# acq07.net
KiCad netlist of a schematic drawn in EAGLE
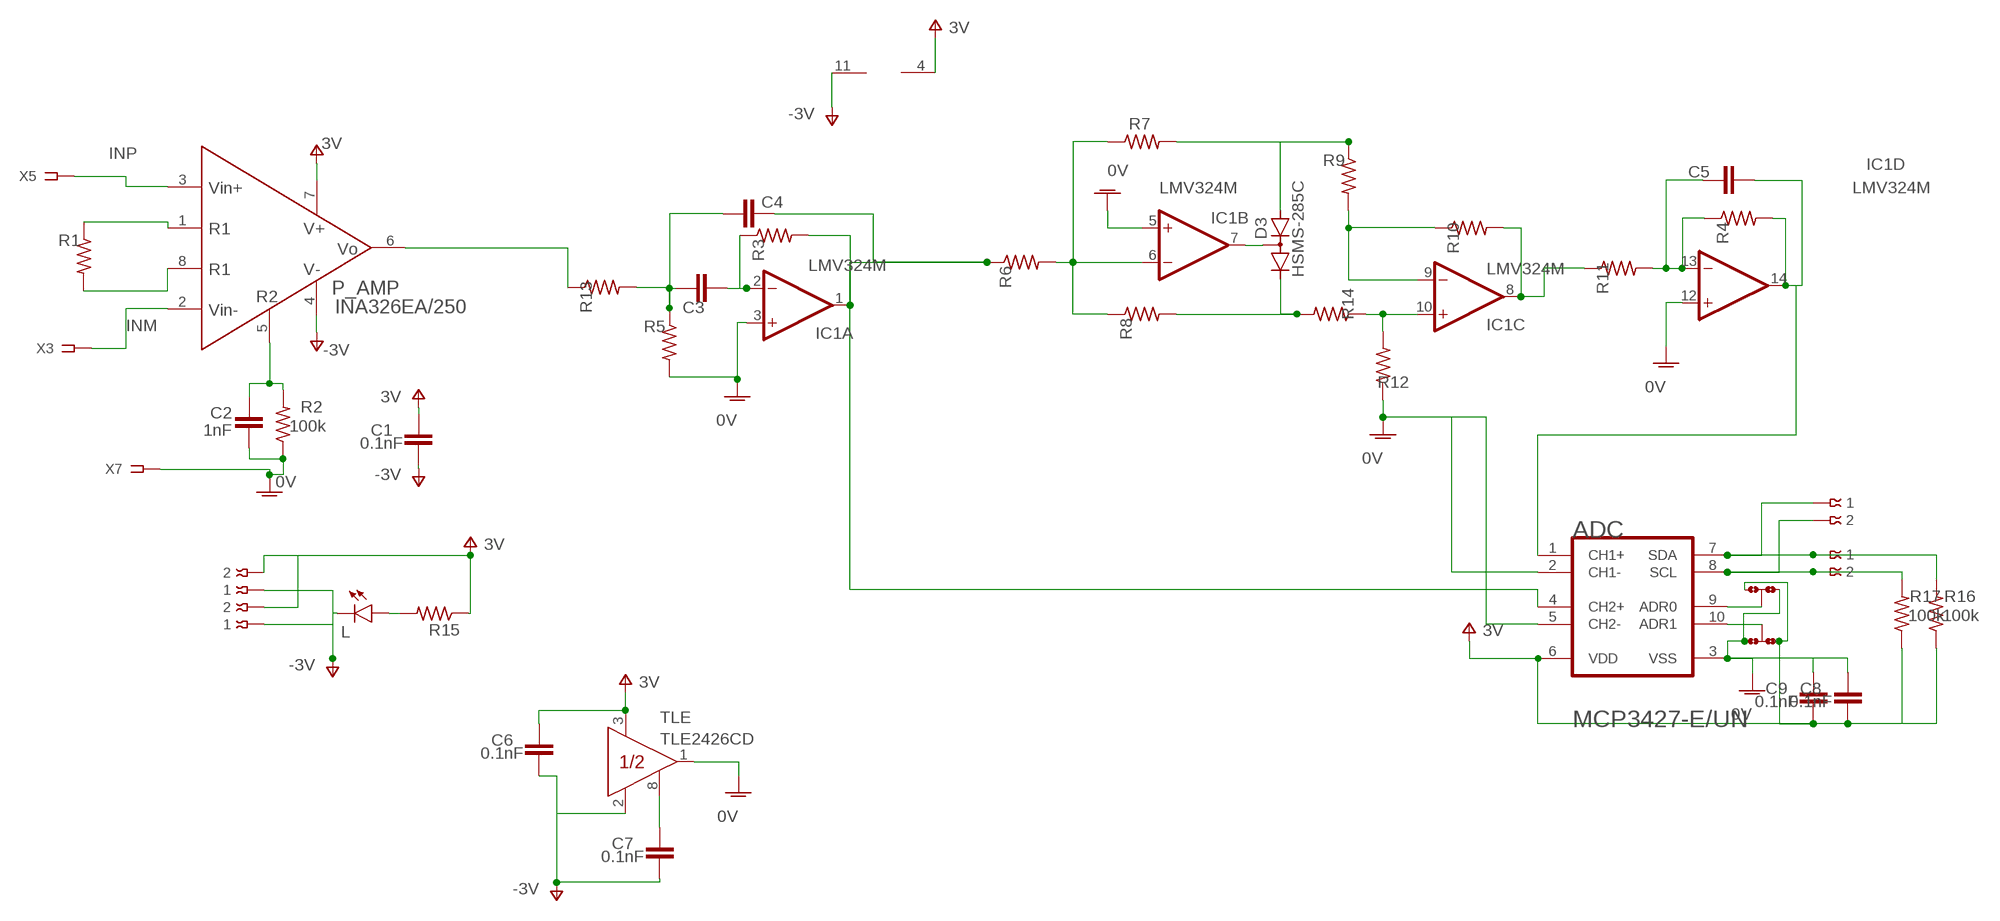
[diagram p0: schematic, sheet 1]

(export (version "E")
  (design (tool "Eeschema 10.0.6"))
  (components
    (comp (ref "A1")
      (value "0R-JUMPC")
      (footprint "eagle-import:C0R-JMP")
      (libsource (lib "eagle-import") (part "0R-JUMPC"))
    )
    (comp (ref "A2")
      (value "0R-JUMPC")
      (footprint "eagle-import:C0R-JMP")
      (libsource (lib "eagle-import") (part "0R-JUMPC"))
    )
    (comp (ref "ADC")
      (value "MICROCHIP_MCP3427-E-UNMICROCHIP_MCP3427-E-UN_0_0")
      (footprint "eagle-import:MICROCHIP_MCP3427-E-UN_0")
      (fields (field (name "MF") "Microchip") (field (name "MPN") "MCP3427-E/UN"))
      (libsource (lib "eagle-import") (part "MICROCHIP_MCP3427-E-UNMICROCHIP_MCP3427-E-UN_0_0"))
    )
    (comp (ref "C1")
      (value "0.1nF")
      (footprint "eagle-import:C0201")
      (libsource (lib "eagle-import") (part "C-EUC0201"))
    )
    (comp (ref "C2")
      (value "1nF")
      (footprint "eagle-import:C0201")
      (libsource (lib "eagle-import") (part "C-EUC0201"))
    )
    (comp (ref "C3")
      (value "0.1nF")
      (footprint "eagle-import:C0201")
      (libsource (lib "eagle-import") (part "C-EUC0201"))
    )
    (comp (ref "C4")
      (value "0.1nF")
      (footprint "eagle-import:C0201")
      (libsource (lib "eagle-import") (part "C-EUC0201"))
    )
    (comp (ref "C5")
      (value "0.1nF")
      (footprint "eagle-import:C0201")
      (libsource (lib "eagle-import") (part "C-EUC0201"))
    )
    (comp (ref "C6")
      (value "0.1nF")
      (footprint "eagle-import:C0201")
      (libsource (lib "eagle-import") (part "C-EUC0201"))
    )
    (comp (ref "C7")
      (value "0.1nF")
      (footprint "eagle-import:C0201")
      (libsource (lib "eagle-import") (part "C-EUC0201"))
    )
    (comp (ref "C8")
      (value "0.1nF")
      (footprint "eagle-import:C0201")
      (libsource (lib "eagle-import") (part "C-EUC0201"))
    )
    (comp (ref "C9")
      (value "0.1nF")
      (footprint "eagle-import:C0201")
      (libsource (lib "eagle-import") (part "C-EUC0201"))
    )
    (comp (ref "D3")
      (value "HSMS-285C")
      (footprint "eagle-import:SOT323")
      (libsource (lib "eagle-import") (part "HSMS-285C"))
    )
    (comp (ref "IC1")
      (value "LMV324M")
      (footprint "eagle-import:SO14")
      (fields (field (name "SPICEPREFIX") "J"))
      (libsource (lib "eagle-import") (part "LMV324?M"))
    )
    (comp (ref "L")
      (value "LEDCHIP-LED0603")
      (footprint "eagle-import:CHIP-LED0603")
      (libsource (lib "eagle-import") (part "LEDCHIP-LED0603"))
    )
    (comp (ref "P_AMP")
      (value "INA326EA/250")
      (footprint "eagle-import:SOP65P490X110-8N")
      (fields (field (name "DIGI-KEY_PART_NUMBER") "296-15312-1-ND") (field (name "MF") "Texas Instruments"))
      (libsource (lib "eagle-import") (part "INA326EA/250"))
    )
    (comp (ref "R1")
      (value "100k")
      (footprint "eagle-import:R0201")
      (libsource (lib "eagle-import") (part "R-US_R0201"))
    )
    (comp (ref "R2")
      (value "100k")
      (footprint "eagle-import:R0201")
      (libsource (lib "eagle-import") (part "R-US_R0201"))
    )
    (comp (ref "R3")
      (value "100k")
      (footprint "eagle-import:R0201")
      (libsource (lib "eagle-import") (part "R-US_R0201"))
    )
    (comp (ref "R4")
      (value "100k")
      (footprint "eagle-import:R0201")
      (libsource (lib "eagle-import") (part "R-US_R0201"))
    )
    (comp (ref "R5")
      (value "100k")
      (footprint "eagle-import:R0201")
      (libsource (lib "eagle-import") (part "R-US_R0201"))
    )
    (comp (ref "R6")
      (value "100k")
      (footprint "eagle-import:R0201")
      (libsource (lib "eagle-import") (part "R-US_R0201"))
    )
    (comp (ref "R7")
      (value "100k")
      (footprint "eagle-import:R0201")
      (libsource (lib "eagle-import") (part "R-US_R0201"))
    )
    (comp (ref "R8")
      (value "100k")
      (footprint "eagle-import:R0201")
      (libsource (lib "eagle-import") (part "R-US_R0201"))
    )
    (comp (ref "R9")
      (value "100k")
      (footprint "eagle-import:R0201")
      (libsource (lib "eagle-import") (part "R-US_R0201"))
    )
    (comp (ref "R10")
      (value "100k")
      (footprint "eagle-import:R0201")
      (libsource (lib "eagle-import") (part "R-US_R0201"))
    )
    (comp (ref "R11")
      (value "100k")
      (footprint "eagle-import:R0201")
      (libsource (lib "eagle-import") (part "R-US_R0201"))
    )
    (comp (ref "R12")
      (value "100k")
      (footprint "eagle-import:R0201")
      (libsource (lib "eagle-import") (part "R-US_R0201"))
    )
    (comp (ref "R13")
      (value "100k")
      (footprint "eagle-import:R0201")
      (libsource (lib "eagle-import") (part "R-US_R0201"))
    )
    (comp (ref "R14")
      (value "100k")
      (footprint "eagle-import:R0201")
      (libsource (lib "eagle-import") (part "R-US_R0201"))
    )
    (comp (ref "R15")
      (value "R-US_R0201")
      (footprint "eagle-import:R0201")
      (libsource (lib "eagle-import") (part "R-US_R0201"))
    )
    (comp (ref "R16")
      (value "100k")
      (footprint "eagle-import:R0201")
      (libsource (lib "eagle-import") (part "R-US_R0201"))
    )
    (comp (ref "R17")
      (value "100k")
      (footprint "eagle-import:R0201")
      (libsource (lib "eagle-import") (part "R-US_R0201"))
    )
    (comp (ref "TLE")
      (value "TLE2426CD")
      (footprint "eagle-import:SO-8")
      (libsource (lib "eagle-import") (part "TLE2426DC"))
    )
    (comp (ref "X1")
      (value "009176002")
      (footprint "eagle-import:009176002")
      (fields (field (name "MPN") "009176002001006"))
      (libsource (lib "eagle-import") (part "00917?0026"))
    )
    (comp (ref "X2")
      (value "009176002")
      (footprint "eagle-import:009176002")
      (fields (field (name "MPN") "009176002001006"))
      (libsource (lib "eagle-import") (part "00917?0026"))
    )
    (comp (ref "X3")
      (value "SSW-101-02-G-S")
      (footprint "eagle-import:SSW-101-02-G-S")
      (fields (field (name "MF") "Samtec Inc."))
      (libsource (lib "eagle-import") (part "SSW-101-02-G-S"))
    )
    (comp (ref "X4")
      (value "009176002")
      (footprint "eagle-import:009176002")
      (fields (field (name "MPN") "009176002001006"))
      (libsource (lib "eagle-import") (part "00917?0026"))
    )
    (comp (ref "X5")
      (value "SSW-101-02-G-S")
      (footprint "eagle-import:SSW-101-02-G-S")
      (fields (field (name "MF") "Samtec Inc."))
      (libsource (lib "eagle-import") (part "SSW-101-02-G-S"))
    )
    (comp (ref "X6")
      (value "009176002")
      (footprint "eagle-import:009176002")
      (fields (field (name "MPN") "009176002001006"))
      (libsource (lib "eagle-import") (part "00917?0026"))
    )
    (comp (ref "X7")
      (value "SSW-101-02-G-S")
      (footprint "eagle-import:SSW-101-02-G-S")
      (fields (field (name "MF") "Samtec Inc."))
      (libsource (lib "eagle-import") (part "SSW-101-02-G-S"))
    )
  )
  (nets
    (net (code "1") (name "-3V") (class "Default")
      (node (ref "C1") (pin "2") (pinfunction "2_2") (pintype "passive"))
      (node (ref "C6") (pin "2") (pinfunction "2_2") (pintype "passive"))
      (node (ref "C7") (pin "2") (pinfunction "2_2") (pintype "passive"))
      (node (ref "IC1") (pin "11") (pinfunction "V-_11") (pintype "power_in"))
      (node (ref "L") (pin "C") (pinfunction "C_C") (pintype "passive"))
      (node (ref "P_AMP") (pin "4") (pinfunction "V-_4") (pintype "power_in"))
      (node (ref "TLE") (pin "2") (pinfunction "COM_2") (pintype "passive"))
      (node (ref "X1") (pin "1") (pinfunction "1_1") (pintype "passive"))
      (node (ref "X4") (pin "1") (pinfunction "1_1") (pintype "passive"))
    )
    (net (code "2") (name "/INM") (class "Default")
      (node (ref "P_AMP") (pin "2") (pinfunction "VIN-_2") (pintype "input"))
      (node (ref "X3") (pin "1") (pinfunction "1_1") (pintype "passive"))
    )
    (net (code "3") (name "/INP") (class "Default")
      (node (ref "P_AMP") (pin "3") (pinfunction "VIN+_3") (pintype "input"))
      (node (ref "X5") (pin "1") (pinfunction "1_1") (pintype "passive"))
    )
    (net (code "4") (name "0V") (class "Default")
      (node (ref "A1") (pin "1") (pinfunction "1_1") (pintype "passive"))
      (node (ref "A2") (pin "1") (pinfunction "1_1") (pintype "passive"))
      (node (ref "ADC") (pin "2") (pinfunction "CH1-_2") (pintype "input"))
      (node (ref "ADC") (pin "3") (pinfunction "VSS_3") (pintype "power_in"))
      (node (ref "ADC") (pin "5") (pinfunction "CH2-_5") (pintype "input"))
      (node (ref "C2") (pin "1") (pinfunction "1_1") (pintype "passive"))
      (node (ref "C8") (pin "1") (pinfunction "1_1") (pintype "passive"))
      (node (ref "C9") (pin "1") (pinfunction "1_1") (pintype "passive"))
      (node (ref "IC1") (pin "12") (pinfunction "+IN_12") (pintype "input"))
      (node (ref "IC1") (pin "3") (pinfunction "+IN_3") (pintype "input"))
      (node (ref "IC1") (pin "5") (pinfunction "+IN_5") (pintype "input"))
      (node (ref "R12") (pin "1") (pinfunction "1_1") (pintype "passive"))
      (node (ref "R2") (pin "1") (pinfunction "1_1") (pintype "passive"))
      (node (ref "R5") (pin "2") (pinfunction "2_2") (pintype "passive"))
      (node (ref "TLE") (pin "1") (pinfunction "OUT_1") (pintype "passive"))
      (node (ref "X7") (pin "1") (pinfunction "1_1") (pintype "passive"))
    )
    (net (code "5") (name "3V") (class "Default")
      (node (ref "A1") (pin "3") (pinfunction "3_3") (pintype "passive"))
      (node (ref "A2") (pin "3") (pinfunction "3_3") (pintype "passive"))
      (node (ref "ADC") (pin "6") (pinfunction "VDD_6") (pintype "power_in"))
      (node (ref "C1") (pin "1") (pinfunction "1_1") (pintype "passive"))
      (node (ref "C6") (pin "1") (pinfunction "1_1") (pintype "passive"))
      (node (ref "C8") (pin "2") (pinfunction "2_2") (pintype "passive"))
      (node (ref "C9") (pin "2") (pinfunction "2_2") (pintype "passive"))
      (node (ref "IC1") (pin "4") (pinfunction "V+_4") (pintype "power_in"))
      (node (ref "P_AMP") (pin "7") (pinfunction "V+_7") (pintype "power_in"))
      (node (ref "R15") (pin "1") (pinfunction "1_1") (pintype "passive"))
      (node (ref "R16") (pin "1") (pinfunction "1_1") (pintype "passive"))
      (node (ref "R17") (pin "1") (pinfunction "1_1") (pintype "passive"))
      (node (ref "TLE") (pin "3") (pinfunction "IN_3") (pintype "passive"))
      (node (ref "X1") (pin "2") (pinfunction "2_2") (pintype "passive"))
      (node (ref "X4") (pin "2") (pinfunction "2_2") (pintype "passive"))
    )
    (net (code "6") (name "Net-(ADC-ADR0)") (class "Default")
      (node (ref "A1") (pin "2") (pinfunction "2_2") (pintype "passive"))
      (node (ref "ADC") (pin "9") (pinfunction "ADR0_9") (pintype "passive"))
    )
    (net (code "7") (name "Net-(ADC-ADR1)") (class "Default")
      (node (ref "A2") (pin "2") (pinfunction "2_2") (pintype "passive"))
      (node (ref "ADC") (pin "10") (pinfunction "ADR1_10") (pintype "passive"))
    )
    (net (code "8") (name "Net-(ADC-CH1+)") (class "Default")
      (node (ref "ADC") (pin "1") (pinfunction "CH1+_1") (pintype "input"))
      (node (ref "C5") (pin "2") (pinfunction "2_2") (pintype "passive"))
      (node (ref "IC1") (pin "14") (pinfunction "OUT_14") (pintype "output"))
      (node (ref "R4") (pin "2") (pinfunction "2_2") (pintype "passive"))
    )
    (net (code "9") (name "Net-(ADC-CH2+)") (class "Default")
      (node (ref "ADC") (pin "4") (pinfunction "CH2+_4") (pintype "input"))
      (node (ref "C4") (pin "1") (pinfunction "1_1") (pintype "passive"))
      (node (ref "IC1") (pin "1") (pinfunction "OUT_1") (pintype "output"))
      (node (ref "R3") (pin "2") (pinfunction "2_2") (pintype "passive"))
      (node (ref "R6") (pin "1") (pinfunction "1_1") (pintype "passive"))
    )
    (net (code "10") (name "Net-(ADC-SCL)") (class "Default")
      (node (ref "ADC") (pin "8") (pinfunction "SCL_8") (pintype "input"))
      (node (ref "R17") (pin "2") (pinfunction "2_2") (pintype "passive"))
      (node (ref "X2") (pin "2") (pinfunction "2_2") (pintype "passive"))
      (node (ref "X6") (pin "2") (pinfunction "2_2") (pintype "passive"))
    )
    (net (code "11") (name "Net-(ADC-SDA)") (class "Default")
      (node (ref "ADC") (pin "7") (pinfunction "SDA_7") (pintype "bidirectional"))
      (node (ref "R16") (pin "2") (pinfunction "2_2") (pintype "passive"))
      (node (ref "X2") (pin "1") (pinfunction "1_1") (pintype "passive"))
      (node (ref "X6") (pin "1") (pinfunction "1_1") (pintype "passive"))
    )
    (net (code "12") (name "Net-(C3-Pad2)") (class "Default")
      (node (ref "C3") (pin "2") (pinfunction "2_2") (pintype "passive"))
      (node (ref "C4") (pin "2") (pinfunction "2_2") (pintype "passive"))
      (node (ref "R13") (pin "2") (pinfunction "2_2") (pintype "passive"))
      (node (ref "R5") (pin "1") (pinfunction "1_1") (pintype "passive"))
    )
    (net (code "13") (name "Net-(D3-A)") (class "Default")
      (node (ref "D3") (pin "1") (pinfunction "A_1") (pintype "passive"))
      (node (ref "R7") (pin "2") (pinfunction "2_2") (pintype "passive"))
      (node (ref "R9") (pin "1") (pinfunction "1_1") (pintype "passive"))
    )
    (net (code "14") (name "Net-(D3-AC)") (class "Default")
      (node (ref "D3") (pin "3") (pinfunction "AC_3") (pintype "passive"))
      (node (ref "IC1") (pin "7") (pinfunction "OUT_7") (pintype "output"))
    )
    (net (code "15") (name "Net-(D3-C)") (class "Default")
      (node (ref "D3") (pin "2") (pinfunction "C_2") (pintype "passive"))
      (node (ref "R14") (pin "2") (pinfunction "2_2") (pintype "passive"))
      (node (ref "R8") (pin "2") (pinfunction "2_2") (pintype "passive"))
    )
    (net (code "16") (name "Net-(IC1A--IN)") (class "Default")
      (node (ref "C3") (pin "1") (pinfunction "1_1") (pintype "passive"))
      (node (ref "IC1") (pin "2") (pinfunction "-IN_2") (pintype "input"))
      (node (ref "R3") (pin "1") (pinfunction "1_1") (pintype "passive"))
    )
    (net (code "17") (name "Net-(IC1B--IN)") (class "Default")
      (node (ref "IC1") (pin "6") (pinfunction "-IN_6") (pintype "input"))
      (node (ref "R6") (pin "2") (pinfunction "2_2") (pintype "passive"))
      (node (ref "R7") (pin "1") (pinfunction "1_1") (pintype "passive"))
      (node (ref "R8") (pin "1") (pinfunction "1_1") (pintype "passive"))
    )
    (net (code "18") (name "Net-(IC1C-+IN)") (class "Default")
      (node (ref "IC1") (pin "10") (pinfunction "+IN_10") (pintype "input"))
      (node (ref "R12") (pin "2") (pinfunction "2_2") (pintype "passive"))
      (node (ref "R14") (pin "1") (pinfunction "1_1") (pintype "passive"))
    )
    (net (code "19") (name "Net-(IC1C--IN)") (class "Default")
      (node (ref "IC1") (pin "9") (pinfunction "-IN_9") (pintype "input"))
      (node (ref "R10") (pin "1") (pinfunction "1_1") (pintype "passive"))
      (node (ref "R9") (pin "2") (pinfunction "2_2") (pintype "passive"))
    )
    (net (code "20") (name "Net-(IC1C-OUT)") (class "Default")
      (node (ref "IC1") (pin "8") (pinfunction "OUT_8") (pintype "output"))
      (node (ref "R10") (pin "2") (pinfunction "2_2") (pintype "passive"))
      (node (ref "R11") (pin "1") (pinfunction "1_1") (pintype "passive"))
    )
    (net (code "21") (name "Net-(IC1D--IN)") (class "Default")
      (node (ref "C5") (pin "1") (pinfunction "1_1") (pintype "passive"))
      (node (ref "IC1") (pin "13") (pinfunction "-IN_13") (pintype "input"))
      (node (ref "R11") (pin "2") (pinfunction "2_2") (pintype "passive"))
      (node (ref "R4") (pin "1") (pinfunction "1_1") (pintype "passive"))
    )
    (net (code "22") (name "Net-(L-PadA)") (class "Default")
      (node (ref "L") (pin "A") (pinfunction "A_A") (pintype "passive"))
      (node (ref "R15") (pin "2") (pinfunction "2_2") (pintype "passive"))
    )
    (net (code "23") (name "Net-(P_AMP-R1)") (class "Default")
      (node (ref "P_AMP") (pin "8") (pinfunction "R1_8") (pintype "input"))
      (node (ref "R1") (pin "2") (pinfunction "2_2") (pintype "passive"))
    )
    (net (code "24") (name "Net-(P_AMP-R1_2)") (class "Default")
      (node (ref "P_AMP") (pin "1") (pinfunction "R1_2_1") (pintype "input"))
      (node (ref "R1") (pin "1") (pinfunction "1_1") (pintype "passive"))
    )
    (net (code "25") (name "Net-(P_AMP-R2)") (class "Default")
      (node (ref "C2") (pin "2") (pinfunction "2_2") (pintype "passive"))
      (node (ref "P_AMP") (pin "5") (pinfunction "R2_5") (pintype "input"))
      (node (ref "R2") (pin "2") (pinfunction "2_2") (pintype "passive"))
    )
    (net (code "26") (name "Net-(P_AMP-VO)") (class "Default")
      (node (ref "P_AMP") (pin "6") (pinfunction "VO_6") (pintype "output"))
      (node (ref "R13") (pin "1") (pinfunction "1_1") (pintype "passive"))
    )
    (net (code "27") (name "Net-(TLE-NR)") (class "Default")
      (node (ref "C7") (pin "1") (pinfunction "1_1") (pintype "passive"))
      (node (ref "TLE") (pin "8") (pinfunction "NR_8") (pintype "passive"))
    )
  )
)
